# sonoff_DIY_3_gang_Dip_version-V_1_1_new.net
KiCad netlist of a schematic drawn in EAGLE
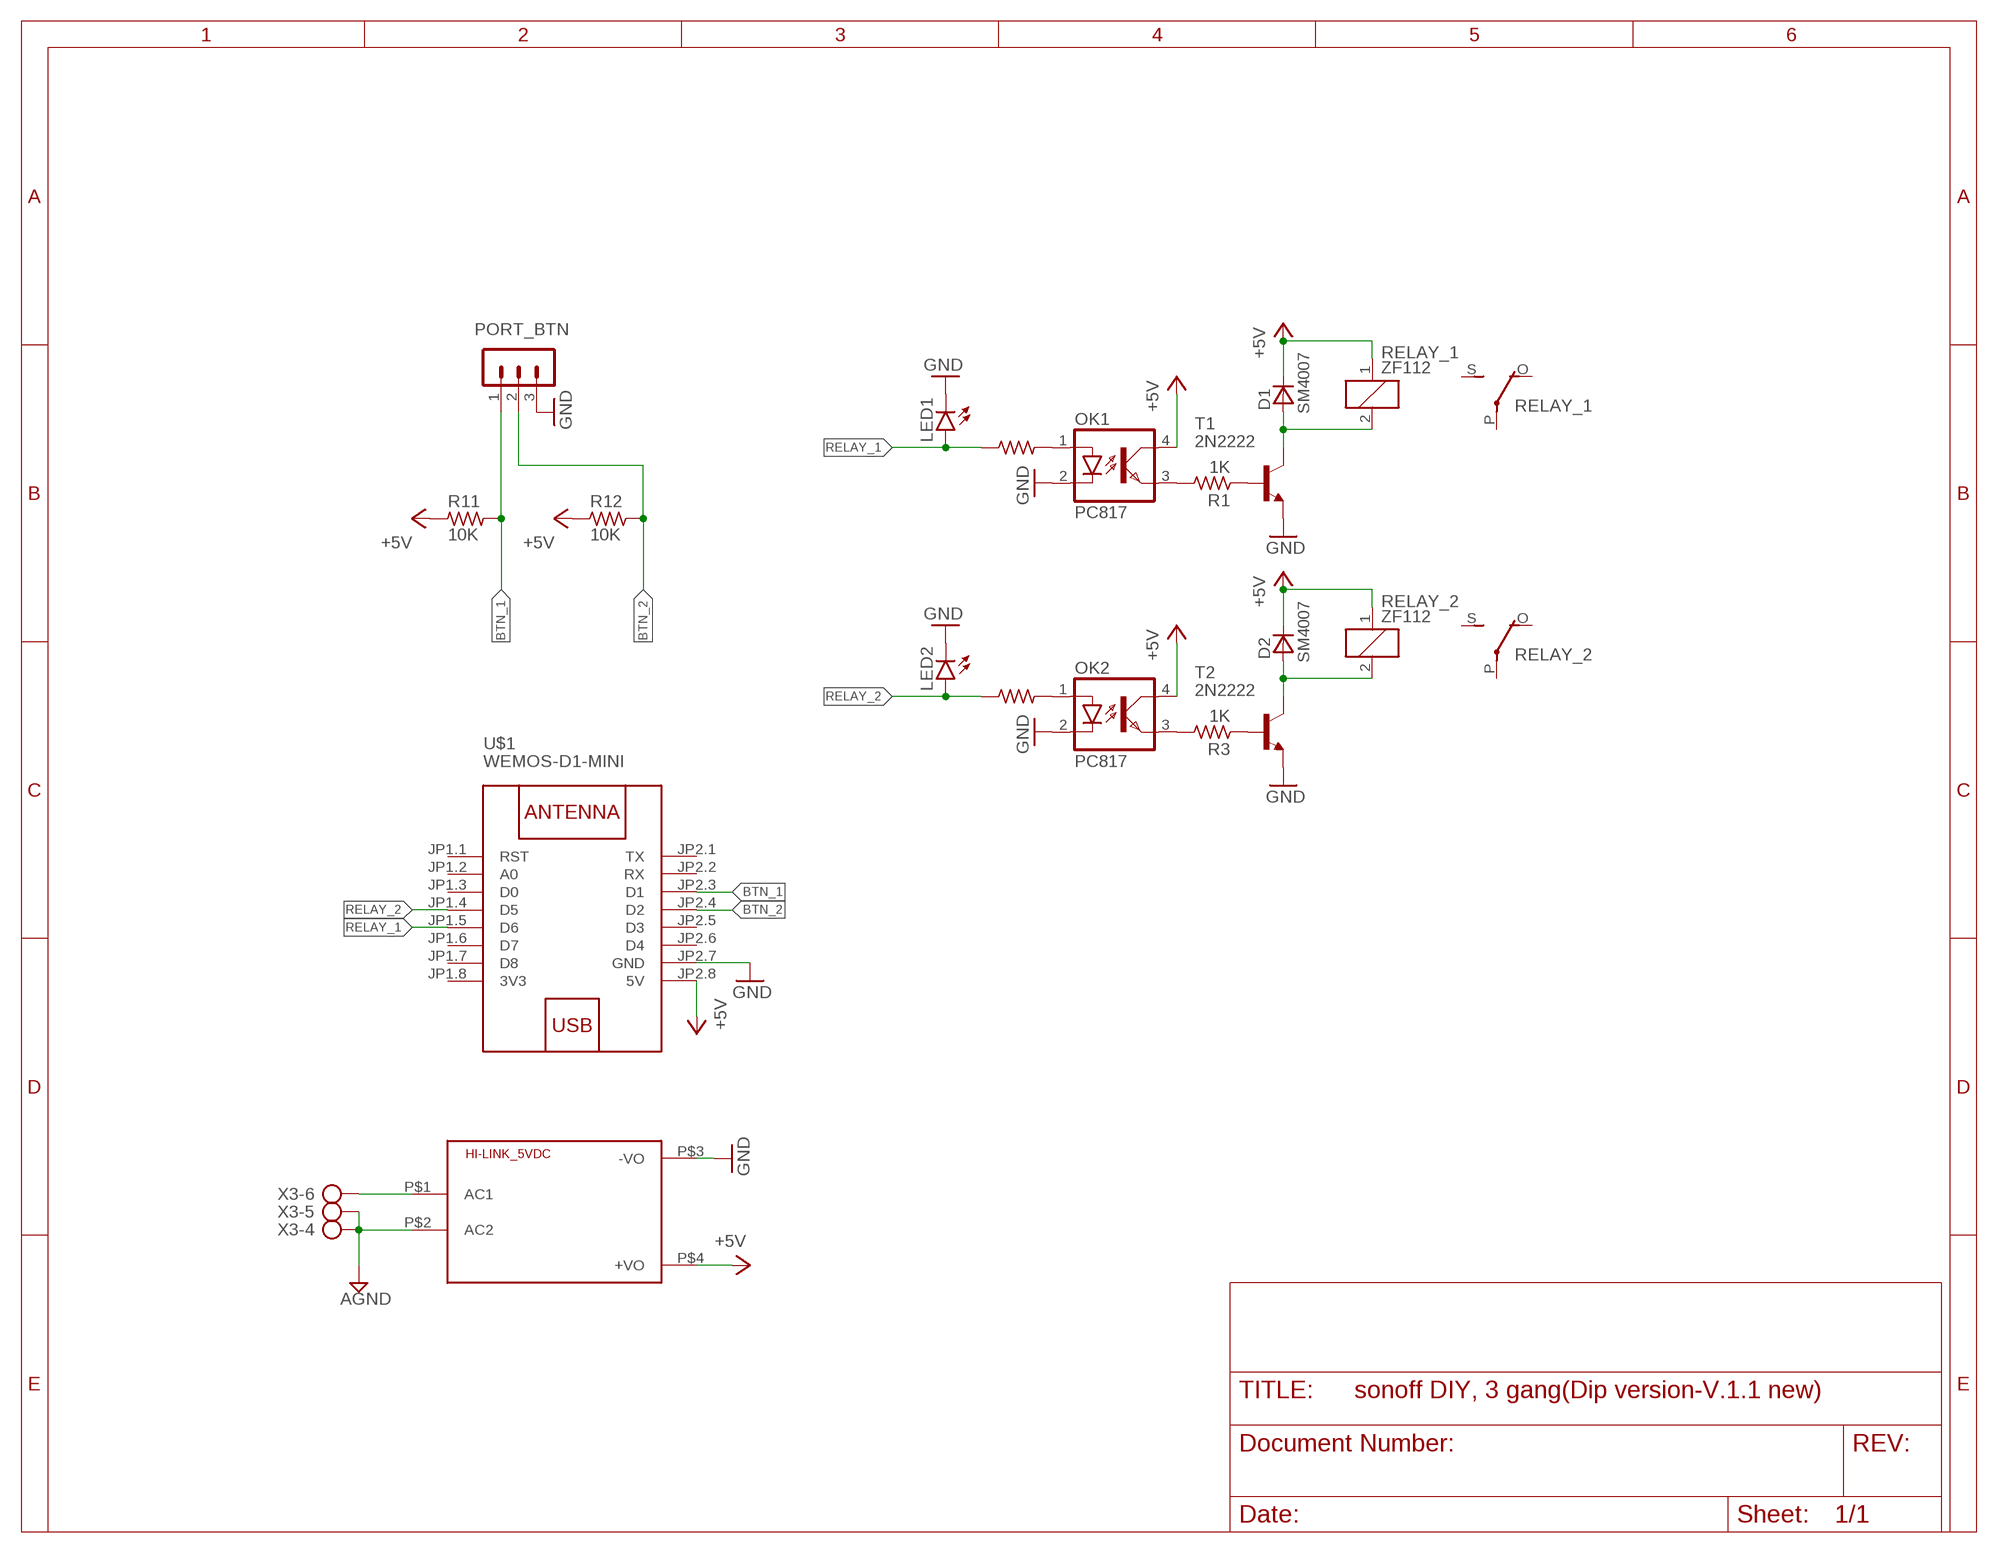
[diagram p0: schematic, sheet 1]

(export (version "E")
  (design (tool "Eeschema 10.0.6"))
  (components
    (comp (ref "D1")
      (value "SM4007")
      (footprint "eagle-import:MELF-MLL41")
      (libsource (lib "eagle-import") (part "SM4007"))
    )
    (comp (ref "D2")
      (value "SM4007")
      (footprint "eagle-import:MELF-MLL41")
      (libsource (lib "eagle-import") (part "SM4007"))
    )
    (comp (ref "HI-LINK_5VDC")
      (value "HLK-PM013W")
      (footprint "eagle-import:HLK-PM01")
      (libsource (lib "eagle-import") (part "HLK-PM013W"))
    )
    (comp (ref "LED1")
      (value "LED3MM")
      (footprint "eagle-import:LED3MM")
      (libsource (lib "eagle-import") (part "LED3MM"))
    )
    (comp (ref "LED2")
      (value "LED3MM")
      (footprint "eagle-import:LED3MM")
      (libsource (lib "eagle-import") (part "LED3MM"))
    )
    (comp (ref "OK1")
      (value "PC817")
      (footprint "eagle-import:DIL04")
      (fields (field (name "MPN") "PC817X4J000F"))
      (libsource (lib "eagle-import") (part "PC817"))
    )
    (comp (ref "OK2")
      (value "PC817")
      (footprint "eagle-import:DIL04")
      (fields (field (name "MPN") "PC817X4J000F"))
      (libsource (lib "eagle-import") (part "PC817"))
    )
    (comp (ref "PORT_BTN")
      (value "MA03-1")
      (footprint "eagle-import:MA03-1")
      (libsource (lib "eagle-import") (part "MA03-1"))
    )
    (comp (ref "R1")
      (value "1K")
      (footprint "eagle-import:R0805")
      (libsource (lib "eagle-import") (part "R_0805"))
    )
    (comp (ref "R2")
      (value "1K")
      (footprint "eagle-import:R0805")
      (libsource (lib "eagle-import") (part "R_0805"))
    )
    (comp (ref "R3")
      (value "1K")
      (footprint "eagle-import:R0805")
      (libsource (lib "eagle-import") (part "R_0805"))
    )
    (comp (ref "R4")
      (value "1K")
      (footprint "eagle-import:R0805")
      (libsource (lib "eagle-import") (part "R_0805"))
    )
    (comp (ref "R11")
      (value "10K")
      (footprint "eagle-import:R0805")
      (libsource (lib "eagle-import") (part "R_0805"))
    )
    (comp (ref "R12")
      (value "10K")
      (footprint "eagle-import:R0805")
      (libsource (lib "eagle-import") (part "R_0805"))
    )
    (comp (ref "RELAY_1")
      (value "ZF112")
      (footprint "eagle-import:ZF112")
      (libsource (lib "eagle-import") (part "ZF112"))
    )
    (comp (ref "RELAY_2")
      (value "ZF112")
      (footprint "eagle-import:ZF112")
      (libsource (lib "eagle-import") (part "ZF112"))
    )
    (comp (ref "T1")
      (value "2N2222")
      (footprint "eagle-import:TO18")
      (libsource (lib "eagle-import") (part "2N2222"))
    )
    (comp (ref "T2")
      (value "2N2222")
      (footprint "eagle-import:TO18")
      (libsource (lib "eagle-import") (part "2N2222"))
    )
    (comp (ref "U$1")
      (value "WEMOS-D1-MINI")
      (footprint "eagle-import:WEMOS-D1-MINI")
      (libsource (lib "eagle-import") (part "WEMOS-D1-MINI"))
    )
    (comp (ref "X3")
      (value "SMKDSP_1,5/6")
      (footprint "eagle-import:SMKDSP_1,5_6")
      (fields (field (name "MF") "FARNELL") (field (name "MPN") "1733619"))
      (libsource (lib "eagle-import") (part "SMKDSP_1,5/6"))
    )
  )
  (nets
    (net (code "1") (name "+5V") (class "Default")
      (node (ref "D1") (pin "C") (pinfunction "C_C") (pintype "passive"))
      (node (ref "D2") (pin "C") (pinfunction "C_C") (pintype "passive"))
      (node (ref "HI-LINK_5VDC") (pin "P$4") (pinfunction "+VO_P$4") (pintype "bidirectional"))
      (node (ref "OK1") (pin "4") (pinfunction "COL_4") (pintype "passive"))
      (node (ref "OK2") (pin "4") (pinfunction "COL_4") (pintype "passive"))
      (node (ref "R11") (pin "1") (pinfunction "1_1") (pintype "passive"))
      (node (ref "R12") (pin "1") (pinfunction "1_1") (pintype "passive"))
      (node (ref "RELAY_1") (pin "1") (pinfunction "1_1") (pintype "passive"))
      (node (ref "RELAY_2") (pin "1") (pinfunction "1_1") (pintype "passive"))
      (node (ref "U$1") (pin "JP2.8") (pinfunction "5V_JP2.8") (pintype "power_in"))
    )
    (net (code "2") (name "/3V3") (class "Default")
      (node (ref "U$1") (pin "JP1.8") (pinfunction "3V3_JP1.8") (pintype "power_in"))
    )
    (net (code "3") (name "AGND") (class "Default")
      (node (ref "HI-LINK_5VDC") (pin "P$2") (pinfunction "AC2_P$2") (pintype "bidirectional"))
      (node (ref "X3") (pin "4") (pinfunction "KL_4") (pintype "passive"))
      (node (ref "X3") (pin "5") (pinfunction "KL_5") (pintype "passive"))
    )
    (net (code "4") (name "BTN_1") (class "Default")
      (node (ref "PORT_BTN") (pin "1") (pinfunction "1_1") (pintype "passive"))
      (node (ref "R11") (pin "2") (pinfunction "2_2") (pintype "passive"))
      (node (ref "U$1") (pin "JP2.3") (pinfunction "D1_JP2.3") (pintype "bidirectional"))
    )
    (net (code "5") (name "BTN_2") (class "Default")
      (node (ref "PORT_BTN") (pin "2") (pinfunction "2_2") (pintype "passive"))
      (node (ref "R12") (pin "2") (pinfunction "2_2") (pintype "passive"))
      (node (ref "U$1") (pin "JP2.4") (pinfunction "D2_JP2.4") (pintype "bidirectional"))
    )
    (net (code "6") (name "GND") (class "Default")
      (node (ref "HI-LINK_5VDC") (pin "P$3") (pinfunction "-VO_P$3") (pintype "bidirectional"))
      (node (ref "LED1") (pin "K") (pinfunction "C_K") (pintype "passive"))
      (node (ref "LED2") (pin "K") (pinfunction "C_K") (pintype "passive"))
      (node (ref "OK1") (pin "2") (pinfunction "C_2") (pintype "passive"))
      (node (ref "OK2") (pin "2") (pinfunction "C_2") (pintype "passive"))
      (node (ref "PORT_BTN") (pin "3") (pinfunction "3_3") (pintype "passive"))
      (node (ref "T1") (pin "1") (pinfunction "E_1") (pintype "passive"))
      (node (ref "T2") (pin "1") (pinfunction "E_1") (pintype "passive"))
      (node (ref "U$1") (pin "JP2.7") (pinfunction "GND_JP2.7") (pintype "power_in"))
    )
    (net (code "7") (name "Net-(HI-LINK_5VDC-AC1)") (class "Default")
      (node (ref "HI-LINK_5VDC") (pin "P$1") (pinfunction "AC1_P$1") (pintype "bidirectional"))
      (node (ref "X3") (pin "6") (pinfunction "KL_6") (pintype "passive"))
    )
    (net (code "8") (name "Net-(OK1-A)") (class "Default")
      (node (ref "OK1") (pin "1") (pinfunction "A_1") (pintype "passive"))
      (node (ref "R2") (pin "1") (pinfunction "1_1") (pintype "passive"))
    )
    (net (code "9") (name "Net-(OK1-EMIT)") (class "Default")
      (node (ref "OK1") (pin "3") (pinfunction "EMIT_3") (pintype "passive"))
      (node (ref "R1") (pin "2") (pinfunction "2_2") (pintype "passive"))
    )
    (net (code "10") (name "Net-(OK2-A)") (class "Default")
      (node (ref "OK2") (pin "1") (pinfunction "A_1") (pintype "passive"))
      (node (ref "R4") (pin "1") (pinfunction "1_1") (pintype "passive"))
    )
    (net (code "11") (name "Net-(OK2-EMIT)") (class "Default")
      (node (ref "OK2") (pin "3") (pinfunction "EMIT_3") (pintype "passive"))
      (node (ref "R3") (pin "2") (pinfunction "2_2") (pintype "passive"))
    )
    (net (code "12") (name "Net-(T1-B)") (class "Default")
      (node (ref "R1") (pin "1") (pinfunction "1_1") (pintype "passive"))
      (node (ref "T1") (pin "2") (pinfunction "B_2") (pintype "passive"))
    )
    (net (code "13") (name "Net-(T1-C)") (class "Default")
      (node (ref "D1") (pin "A") (pinfunction "A_A") (pintype "passive"))
      (node (ref "RELAY_1") (pin "2") (pinfunction "2_2") (pintype "passive"))
      (node (ref "T1") (pin "3") (pinfunction "C_3") (pintype "passive"))
    )
    (net (code "14") (name "Net-(T2-B)") (class "Default")
      (node (ref "R3") (pin "1") (pinfunction "1_1") (pintype "passive"))
      (node (ref "T2") (pin "2") (pinfunction "B_2") (pintype "passive"))
    )
    (net (code "15") (name "Net-(T2-C)") (class "Default")
      (node (ref "D2") (pin "A") (pinfunction "A_A") (pintype "passive"))
      (node (ref "RELAY_2") (pin "2") (pinfunction "2_2") (pintype "passive"))
      (node (ref "T2") (pin "3") (pinfunction "C_3") (pintype "passive"))
    )
    (net (code "16") (name "RELAY_1") (class "Default")
      (node (ref "LED1") (pin "A") (pinfunction "A_A") (pintype "passive"))
      (node (ref "R2") (pin "2") (pinfunction "2_2") (pintype "passive"))
      (node (ref "U$1") (pin "JP1.5") (pinfunction "D6_JP1.5") (pintype "bidirectional"))
    )
    (net (code "17") (name "RELAY_2") (class "Default")
      (node (ref "LED2") (pin "A") (pinfunction "A_A") (pintype "passive"))
      (node (ref "R4") (pin "2") (pinfunction "2_2") (pintype "passive"))
      (node (ref "U$1") (pin "JP1.4") (pinfunction "D5_JP1.4") (pintype "bidirectional"))
    )
    (net (code "18") (name "unconnected-(RELAY_1-PadO)") (class "Default")
      (node (ref "RELAY_1") (pin "O") (pinfunction "O_O") (pintype "passive"))
    )
    (net (code "19") (name "unconnected-(RELAY_1-PadP)") (class "Default")
      (node (ref "RELAY_1") (pin "P") (pinfunction "P_P") (pintype "passive"))
    )
    (net (code "20") (name "unconnected-(RELAY_1-PadS)") (class "Default")
      (node (ref "RELAY_1") (pin "S") (pinfunction "S_S") (pintype "passive"))
    )
    (net (code "21") (name "unconnected-(RELAY_2-PadO)") (class "Default")
      (node (ref "RELAY_2") (pin "O") (pinfunction "O_O") (pintype "passive"))
    )
    (net (code "22") (name "unconnected-(RELAY_2-PadP)") (class "Default")
      (node (ref "RELAY_2") (pin "P") (pinfunction "P_P") (pintype "passive"))
    )
    (net (code "23") (name "unconnected-(RELAY_2-PadS)") (class "Default")
      (node (ref "RELAY_2") (pin "S") (pinfunction "S_S") (pintype "passive"))
    )
    (net (code "24") (name "unconnected-(U$1-A0-PadJP1.2)") (class "Default")
      (node (ref "U$1") (pin "JP1.2") (pinfunction "A0_JP1.2") (pintype "bidirectional"))
    )
    (net (code "25") (name "unconnected-(U$1-D0-PadJP1.3)") (class "Default")
      (node (ref "U$1") (pin "JP1.3") (pinfunction "D0_JP1.3") (pintype "bidirectional"))
    )
    (net (code "26") (name "unconnected-(U$1-D3-PadJP2.5)") (class "Default")
      (node (ref "U$1") (pin "JP2.5") (pinfunction "D3_JP2.5") (pintype "bidirectional"))
    )
    (net (code "27") (name "unconnected-(U$1-D4-PadJP2.6)") (class "Default")
      (node (ref "U$1") (pin "JP2.6") (pinfunction "D4_JP2.6") (pintype "bidirectional"))
    )
    (net (code "28") (name "unconnected-(U$1-D7-PadJP1.6)") (class "Default")
      (node (ref "U$1") (pin "JP1.6") (pinfunction "D7_JP1.6") (pintype "bidirectional"))
    )
    (net (code "29") (name "unconnected-(U$1-D8-PadJP1.7)") (class "Default")
      (node (ref "U$1") (pin "JP1.7") (pinfunction "D8_JP1.7") (pintype "bidirectional"))
    )
    (net (code "30") (name "unconnected-(U$1-RST-PadJP1.1)") (class "Default")
      (node (ref "U$1") (pin "JP1.1") (pinfunction "RST_JP1.1") (pintype "bidirectional"))
    )
    (net (code "31") (name "unconnected-(U$1-RX-PadJP2.2)") (class "Default")
      (node (ref "U$1") (pin "JP2.2") (pinfunction "RX_JP2.2") (pintype "bidirectional"))
    )
    (net (code "32") (name "unconnected-(U$1-TX-PadJP2.1)") (class "Default")
      (node (ref "U$1") (pin "JP2.1") (pinfunction "TX_JP2.1") (pintype "bidirectional"))
    )
  )
)
